# DC-DC-Brick-eighth.net
KiCad netlist of a schematic drawn in EAGLE
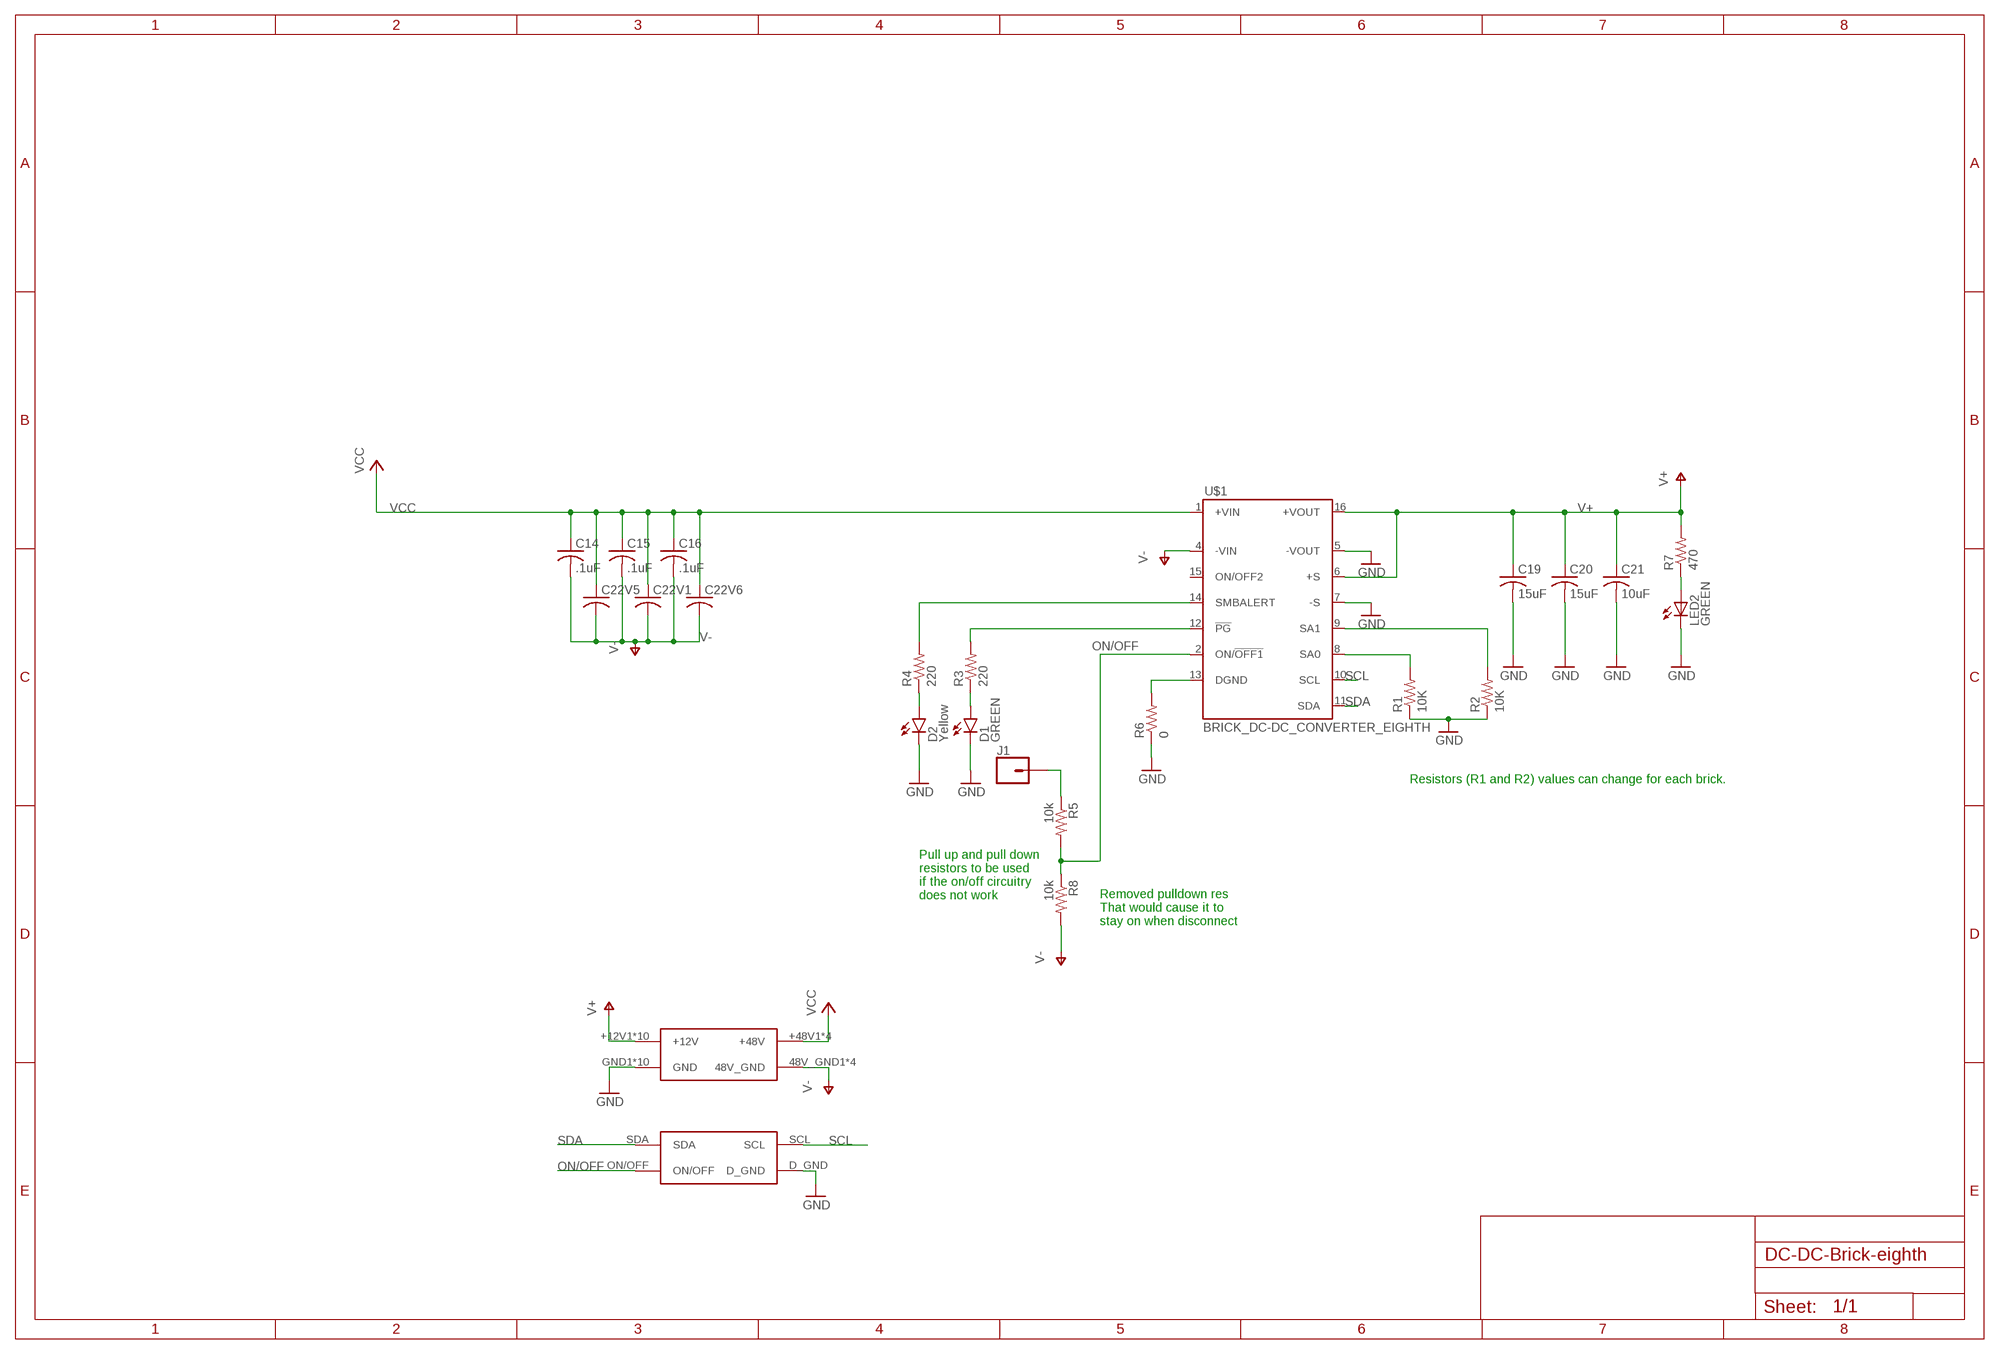
[diagram p0: schematic, sheet 1]

(export (version "E")
  (design (tool "Eeschema 10.0.6"))
  (components
    (comp (ref "C14")
      (value ".1uF")
      (footprint "eagle-import:C0603")
      (libsource (lib "eagle-import") (part "C-USC0603"))
    )
    (comp (ref "C15")
      (value ".1uF")
      (footprint "eagle-import:C0603")
      (libsource (lib "eagle-import") (part "C-USC0603"))
    )
    (comp (ref "C16")
      (value ".1uF")
      (footprint "eagle-import:C0603")
      (libsource (lib "eagle-import") (part "C-USC0603"))
    )
    (comp (ref "C19")
      (value "15uF")
      (footprint "eagle-import:C3216")
      (libsource (lib "eagle-import") (part "C-USC3216"))
    )
    (comp (ref "C20")
      (value "15uF")
      (footprint "eagle-import:C3216")
      (libsource (lib "eagle-import") (part "C-USC3216"))
    )
    (comp (ref "C21")
      (value "10uF")
      (footprint "eagle-import:C0603")
      (libsource (lib "eagle-import") (part "C-USC0603"))
    )
    (comp (ref "C22V1")
      (value "EXTENDED_PAD_CAPACITOR")
      (footprint "eagle-import:MODIFIED-NICHICON-UX-8X10")
      (libsource (lib "eagle-import") (part "EXTENDED_PAD_CAPACITOR"))
    )
    (comp (ref "C22V5")
      (value "EXTENDED_PAD_CAPACITOR")
      (footprint "eagle-import:MODIFIED-NICHICON-UX-8X10")
      (libsource (lib "eagle-import") (part "EXTENDED_PAD_CAPACITOR"))
    )
    (comp (ref "C22V6")
      (value "EXTENDED_PAD_CAPACITOR")
      (footprint "eagle-import:MODIFIED-NICHICON-UX-8X10")
      (libsource (lib "eagle-import") (part "EXTENDED_PAD_CAPACITOR"))
    )
    (comp (ref "D1")
      (value "GREEN")
      (footprint "eagle-import:LED-0603")
      (libsource (lib "eagle-import") (part "LED-GREEN0603"))
    )
    (comp (ref "D2")
      (value "Yellow")
      (footprint "eagle-import:LED-0603")
      (libsource (lib "eagle-import") (part "LED-YELLOW0603"))
    )
    (comp (ref "J1")
      (value "CONN_01")
      (footprint "eagle-import:1X01")
      (libsource (lib "eagle-import") (part "CONN_01"))
    )
    (comp (ref "LED2")
      (value "GREEN")
      (footprint "eagle-import:LED-0603")
      (fields (field (name "PARTNO") "160-1446-1-ND"))
      (libsource (lib "eagle-import") (part "LED0603"))
    )
    (comp (ref "R1")
      (value "10K")
      (footprint "eagle-import:0603-RES")
      (libsource (lib "eagle-import") (part "10KOHM-1/10W-1%(0603)0603"))
    )
    (comp (ref "R2")
      (value "10K")
      (footprint "eagle-import:0603-RES")
      (libsource (lib "eagle-import") (part "10KOHM-1/10W-1%(0603)0603"))
    )
    (comp (ref "R3")
      (value "220")
      (footprint "eagle-import:0603-RES")
      (libsource (lib "eagle-import") (part "1KOHM-1/10W-1%(0603)"))
    )
    (comp (ref "R4")
      (value "220")
      (footprint "eagle-import:0603-RES")
      (libsource (lib "eagle-import") (part "1KOHM-1/10W-1%(0603)"))
    )
    (comp (ref "R5")
      (value "10k")
      (footprint "eagle-import:0603-RES")
      (libsource (lib "eagle-import") (part "1KOHM-1/10W-1%(0603)"))
    )
    (comp (ref "R6")
      (value "0")
      (footprint "eagle-import:0603-RES")
      (libsource (lib "eagle-import") (part "1KOHM-1/10W-1%(0603)"))
    )
    (comp (ref "R7")
      (value "470")
      (footprint "eagle-import:0603-RES")
      (libsource (lib "eagle-import") (part "470OHM1/10W1%(0603)"))
    )
    (comp (ref "R8")
      (value "10k")
      (footprint "eagle-import:0603-RES")
      (libsource (lib "eagle-import") (part "1KOHM-1/10W-1%(0603)"))
    )
    (comp (ref "U$1")
      (value "BRICK_DC-DC_CONVERTER_EIGHTH")
      (footprint "eagle-import:BRICK_DC-DC_CONVERTER_EIGHTH")
      (libsource (lib "eagle-import") (part "BRICK_DC-DC_CONVERTER_EIGHTH"))
    )
    (comp (ref "U$4")
      (value "BRICK_TO_POWER_DIST_WHOLE")
      (footprint "eagle-import:BRICK_TO_POWER_DIST_WHOLE")
      (libsource (lib "eagle-import") (part "BRICK_TO_POWER_DIST_WHOLE"))
    )
  )
  (nets
    (net (code "1") (name "/ON{slash}OFF") (class "Default")
      (node (ref "R5") (pin "2") (pinfunction "2_2") (pintype "passive"))
      (node (ref "R8") (pin "1") (pinfunction "1_1") (pintype "passive"))
      (node (ref "U$1") (pin "2") (pinfunction "ON/~{OFF1}_2") (pintype "bidirectional"))
      (node (ref "U$4") (pin "ON/OFF") (pinfunction "ON/OFF_ON/OFF") (pintype "bidirectional"))
    )
    (net (code "2") (name "/SCL") (class "Default")
      (node (ref "U$1") (pin "10") (pinfunction "SCL_10") (pintype "bidirectional"))
      (node (ref "U$4") (pin "SCL") (pinfunction "SCL_SCL") (pintype "bidirectional"))
    )
    (net (code "3") (name "/SDA") (class "Default")
      (node (ref "U$1") (pin "11") (pinfunction "SDA_11") (pintype "bidirectional"))
      (node (ref "U$4") (pin "SDA") (pinfunction "SDA_SDA") (pintype "bidirectional"))
    )
    (net (code "4") (name "GND") (class "Default")
      (node (ref "C19") (pin "2") (pinfunction "2_2") (pintype "passive"))
      (node (ref "C20") (pin "2") (pinfunction "2_2") (pintype "passive"))
      (node (ref "C21") (pin "2") (pinfunction "2_2") (pintype "passive"))
      (node (ref "D1") (pin "C") (pinfunction "C_C") (pintype "passive"))
      (node (ref "D2") (pin "C") (pinfunction "C_C") (pintype "passive"))
      (node (ref "LED2") (pin "C") (pinfunction "C_C") (pintype "passive"))
      (node (ref "R1") (pin "1") (pinfunction "1_1") (pintype "passive"))
      (node (ref "R2") (pin "1") (pinfunction "1_1") (pintype "passive"))
      (node (ref "R6") (pin "1") (pinfunction "1_1") (pintype "passive"))
      (node (ref "U$1") (pin "5") (pinfunction "-VOUT_5") (pintype "power_in"))
      (node (ref "U$1") (pin "7") (pinfunction "-S_7") (pintype "bidirectional"))
      (node (ref "U$4") (pin "D_GND") (pinfunction "D_GND_D_GND") (pintype "bidirectional"))
      (node (ref "U$4") (pin "GND1") (pinfunction "GND_GND1") (pintype "bidirectional"))
      (node (ref "U$4") (pin "GND10") (pinfunction "GND_GND10") (pintype "bidirectional"))
      (node (ref "U$4") (pin "GND2") (pinfunction "GND_GND2") (pintype "bidirectional"))
      (node (ref "U$4") (pin "GND3") (pinfunction "GND_GND3") (pintype "bidirectional"))
      (node (ref "U$4") (pin "GND4") (pinfunction "GND_GND4") (pintype "bidirectional"))
      (node (ref "U$4") (pin "GND5") (pinfunction "GND_GND5") (pintype "bidirectional"))
      (node (ref "U$4") (pin "GND6") (pinfunction "GND_GND6") (pintype "bidirectional"))
      (node (ref "U$4") (pin "GND7") (pinfunction "GND_GND7") (pintype "bidirectional"))
      (node (ref "U$4") (pin "GND8") (pinfunction "GND_GND8") (pintype "bidirectional"))
      (node (ref "U$4") (pin "GND9") (pinfunction "GND_GND9") (pintype "bidirectional"))
    )
    (net (code "5") (name "Net-(D1-PadA)") (class "Default")
      (node (ref "D1") (pin "A") (pinfunction "A_A") (pintype "passive"))
      (node (ref "R3") (pin "1") (pinfunction "1_1") (pintype "passive"))
    )
    (net (code "6") (name "Net-(D2-PadA)") (class "Default")
      (node (ref "D2") (pin "A") (pinfunction "A_A") (pintype "passive"))
      (node (ref "R4") (pin "1") (pinfunction "1_1") (pintype "passive"))
    )
    (net (code "7") (name "Net-(J1-Pad1)") (class "Default")
      (node (ref "J1") (pin "1") (pinfunction "1_1") (pintype "passive"))
      (node (ref "R5") (pin "1") (pinfunction "1_1") (pintype "passive"))
    )
    (net (code "8") (name "Net-(LED2-PadA)") (class "Default")
      (node (ref "LED2") (pin "A") (pinfunction "A_A") (pintype "passive"))
      (node (ref "R7") (pin "1") (pinfunction "1_1") (pintype "passive"))
    )
    (net (code "9") (name "Net-(U$1-DGND)") (class "Default")
      (node (ref "R6") (pin "2") (pinfunction "2_2") (pintype "passive"))
      (node (ref "U$1") (pin "13") (pinfunction "DGND_13") (pintype "power_in"))
    )
    (net (code "10") (name "Net-(U$1-SA0)") (class "Default")
      (node (ref "R1") (pin "2") (pinfunction "2_2") (pintype "passive"))
      (node (ref "U$1") (pin "8") (pinfunction "SA0_8") (pintype "bidirectional"))
    )
    (net (code "11") (name "Net-(U$1-SA1)") (class "Default")
      (node (ref "R2") (pin "2") (pinfunction "2_2") (pintype "passive"))
      (node (ref "U$1") (pin "9") (pinfunction "SA1_9") (pintype "bidirectional"))
    )
    (net (code "12") (name "Net-(U$1-SMBALERT)") (class "Default")
      (node (ref "R4") (pin "2") (pinfunction "2_2") (pintype "passive"))
      (node (ref "U$1") (pin "14") (pinfunction "SMBALERT_14") (pintype "bidirectional"))
    )
    (net (code "13") (name "Net-(U$1-~{PG})") (class "Default")
      (node (ref "R3") (pin "2") (pinfunction "2_2") (pintype "passive"))
      (node (ref "U$1") (pin "12") (pinfunction "~{PG}_12") (pintype "bidirectional"))
    )
    (net (code "14") (name "V+") (class "Default")
      (node (ref "C19") (pin "1") (pinfunction "1_1") (pintype "passive"))
      (node (ref "C20") (pin "1") (pinfunction "1_1") (pintype "passive"))
      (node (ref "C21") (pin "1") (pinfunction "1_1") (pintype "passive"))
      (node (ref "R7") (pin "2") (pinfunction "2_2") (pintype "passive"))
      (node (ref "U$1") (pin "16") (pinfunction "+VOUT_16") (pintype "power_in"))
      (node (ref "U$1") (pin "6") (pinfunction "+S_6") (pintype "bidirectional"))
      (node (ref "U$4") (pin "+12V1") (pinfunction "+12V_+12V1") (pintype "bidirectional"))
      (node (ref "U$4") (pin "+12V10") (pinfunction "+12V_+12V10") (pintype "bidirectional"))
      (node (ref "U$4") (pin "+12V2") (pinfunction "+12V_+12V2") (pintype "bidirectional"))
      (node (ref "U$4") (pin "+12V3") (pinfunction "+12V_+12V3") (pintype "bidirectional"))
      (node (ref "U$4") (pin "+12V4") (pinfunction "+12V_+12V4") (pintype "bidirectional"))
      (node (ref "U$4") (pin "+12V5") (pinfunction "+12V_+12V5") (pintype "bidirectional"))
      (node (ref "U$4") (pin "+12V6") (pinfunction "+12V_+12V6") (pintype "bidirectional"))
      (node (ref "U$4") (pin "+12V7") (pinfunction "+12V_+12V7") (pintype "bidirectional"))
      (node (ref "U$4") (pin "+12V8") (pinfunction "+12V_+12V8") (pintype "bidirectional"))
      (node (ref "U$4") (pin "+12V9") (pinfunction "+12V_+12V9") (pintype "bidirectional"))
    )
    (net (code "15") (name "V-") (class "Default")
      (node (ref "C14") (pin "2") (pinfunction "2_2") (pintype "passive"))
      (node (ref "C15") (pin "2") (pinfunction "2_2") (pintype "passive"))
      (node (ref "C16") (pin "2") (pinfunction "2_2") (pintype "passive"))
      (node (ref "C22V1") (pin "P$1") (pinfunction "4_P$1") (pintype "passive"))
      (node (ref "C22V5") (pin "P$1") (pinfunction "4_P$1") (pintype "passive"))
      (node (ref "C22V6") (pin "P$1") (pinfunction "4_P$1") (pintype "passive"))
      (node (ref "R8") (pin "2") (pinfunction "2_2") (pintype "passive"))
      (node (ref "U$1") (pin "4") (pinfunction "-VIN_4") (pintype "power_in"))
      (node (ref "U$4") (pin "48V_GND1") (pinfunction "48V_GND_48V_GND1") (pintype "bidirectional"))
      (node (ref "U$4") (pin "48V_GND2") (pinfunction "48V_GND_48V_GND2") (pintype "bidirectional"))
      (node (ref "U$4") (pin "48V_GND3") (pinfunction "48V_GND_48V_GND3") (pintype "bidirectional"))
      (node (ref "U$4") (pin "48V_GND4") (pinfunction "48V_GND_48V_GND4") (pintype "bidirectional"))
    )
    (net (code "16") (name "VCC") (class "Default")
      (node (ref "C14") (pin "1") (pinfunction "1_1") (pintype "passive"))
      (node (ref "C15") (pin "1") (pinfunction "1_1") (pintype "passive"))
      (node (ref "C16") (pin "1") (pinfunction "1_1") (pintype "passive"))
      (node (ref "C22V1") (pin "P$3") (pinfunction "3_P$3") (pintype "passive"))
      (node (ref "C22V5") (pin "P$3") (pinfunction "3_P$3") (pintype "passive"))
      (node (ref "C22V6") (pin "P$3") (pinfunction "3_P$3") (pintype "passive"))
      (node (ref "U$1") (pin "1") (pinfunction "+VIN_1") (pintype "power_in"))
      (node (ref "U$4") (pin "+48V1") (pinfunction "+48V_+48V1") (pintype "bidirectional"))
      (node (ref "U$4") (pin "+48V2") (pinfunction "+48V_+48V2") (pintype "bidirectional"))
      (node (ref "U$4") (pin "+48V3") (pinfunction "+48V_+48V3") (pintype "bidirectional"))
      (node (ref "U$4") (pin "+48V4") (pinfunction "+48V_+48V4") (pintype "bidirectional"))
    )
    (net (code "17") (name "unconnected-(U$1-ON{slash}OFF2-Pad15)") (class "Default")
      (node (ref "U$1") (pin "15") (pinfunction "ON/OFF2_15") (pintype "bidirectional"))
    )
  )
)
